# Programmable_AC_Series_Limiter.net
KiCad netlist of a schematic drawn in EAGLE
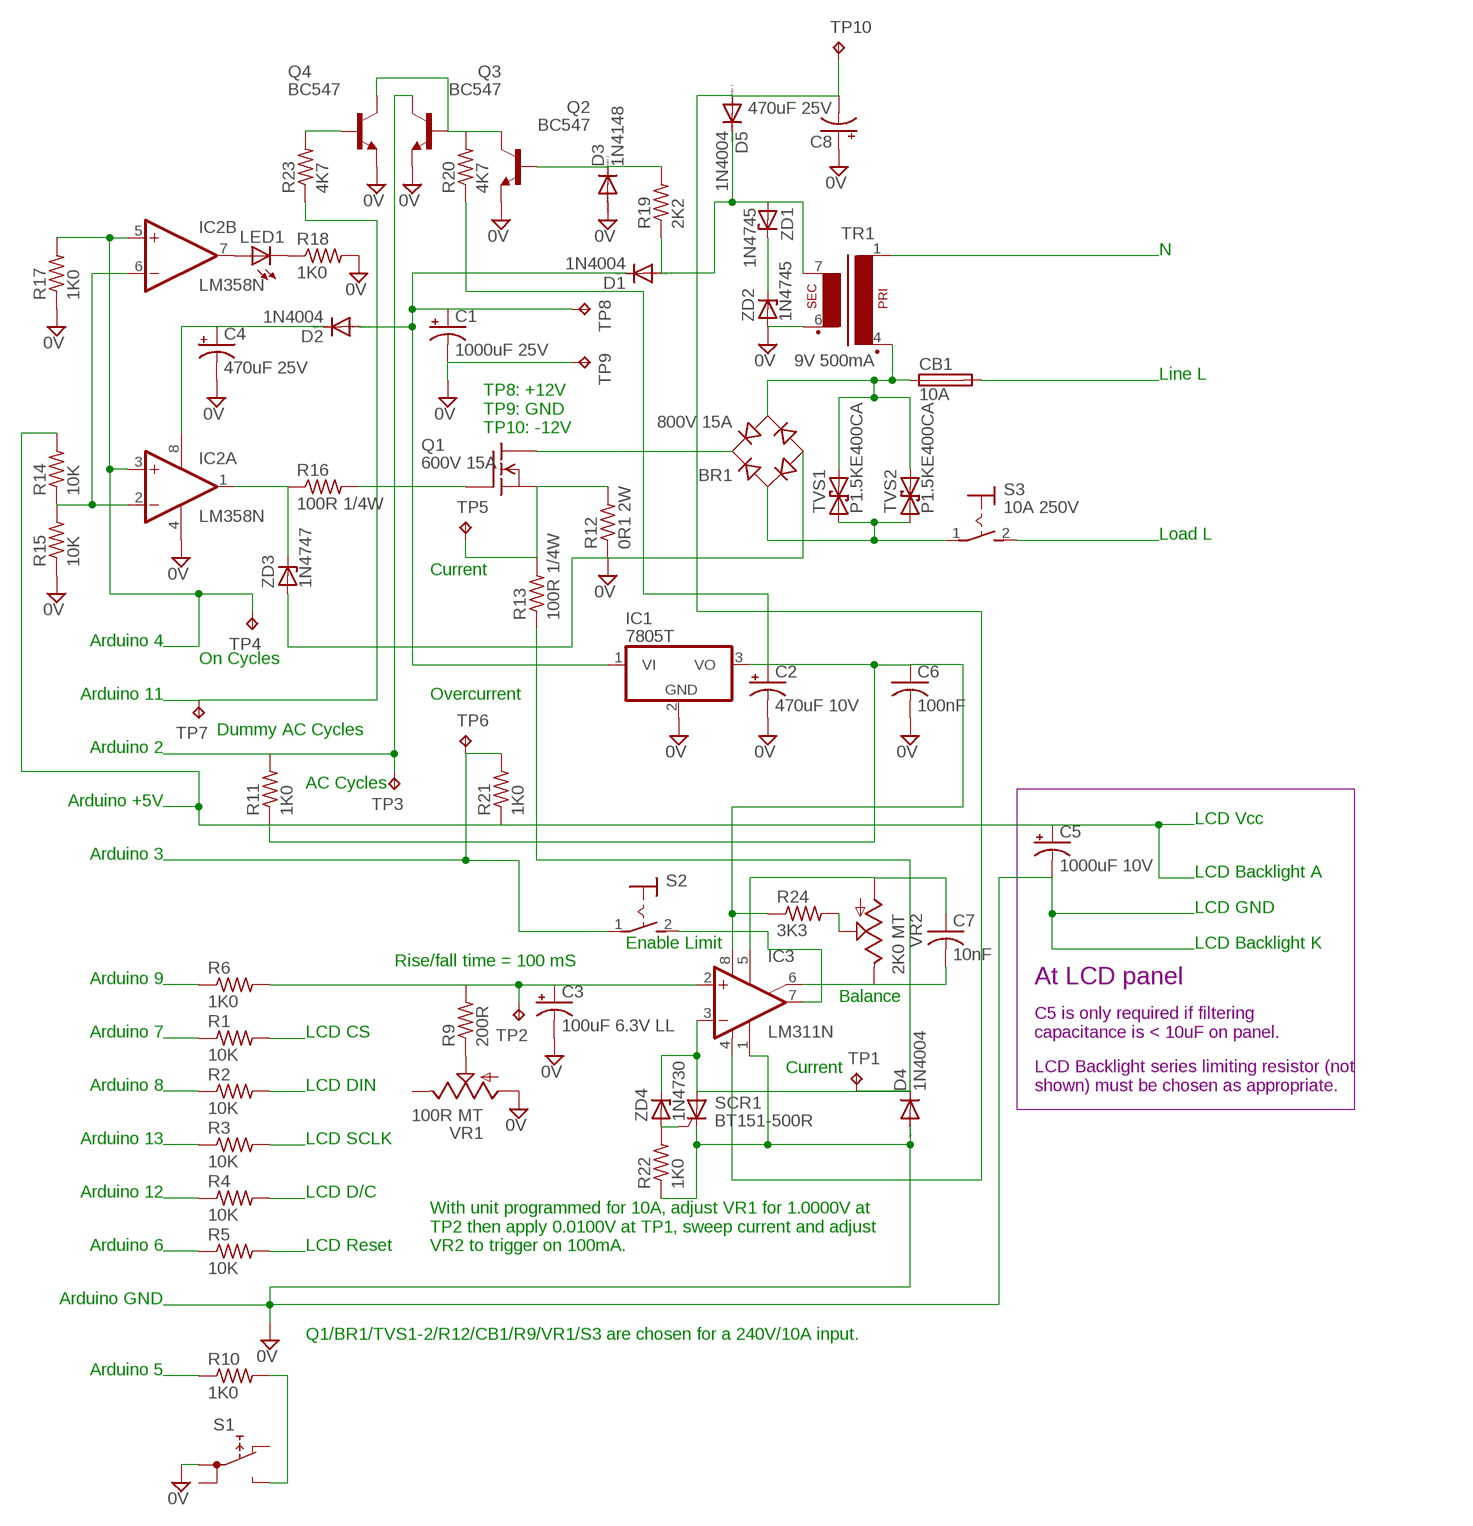
[diagram p0: schematic, sheet 1]

(export (version "E")
  (design (tool "Eeschema 10.0.6"))
  (components
    (comp (ref "BR1")
      (value "800V 15A")
      (footprint "eagle-import:DB")
      (libsource (lib "eagle-import") (part "DB?GDB101"))
    )
    (comp (ref "C1")
      (value "1000uF 25V")
      (footprint "eagle-import:B45181A")
      (libsource (lib "eagle-import") (part "CPOL-USB45181A"))
    )
    (comp (ref "C2")
      (value "470uF 10V")
      (footprint "eagle-import:B45181A")
      (libsource (lib "eagle-import") (part "CPOL-USB45181A"))
    )
    (comp (ref "C3")
      (value "100uF 6.3V LL")
      (footprint "eagle-import:B45181A")
      (libsource (lib "eagle-import") (part "CPOL-USB45181A"))
    )
    (comp (ref "C4")
      (value "470uF 25V")
      (footprint "eagle-import:B45181A")
      (libsource (lib "eagle-import") (part "CPOL-USB45181A"))
    )
    (comp (ref "C5")
      (value "1000uF 10V")
      (footprint "eagle-import:B45181A")
      (libsource (lib "eagle-import") (part "CPOL-USB45181A"))
    )
    (comp (ref "C6")
      (value "100nF")
      (footprint "eagle-import:C025-024X044")
      (libsource (lib "eagle-import") (part "C-US025-024X044"))
    )
    (comp (ref "C7")
      (value "10nF")
      (footprint "eagle-import:C025-024X044")
      (libsource (lib "eagle-import") (part "C-US025-024X044"))
    )
    (comp (ref "C8")
      (value "470uF 25V")
      (footprint "eagle-import:B45181A")
      (libsource (lib "eagle-import") (part "CPOL-USB45181A"))
    )
    (comp (ref "CB1")
      (value "10A")
      (footprint "eagle-import:FUSE_HOLDER_MENTOR-1821")
      (libsource (lib "eagle-import") (part "FUSE1821"))
    )
    (comp (ref "D1")
      (value "1N4004")
      (footprint "eagle-import:DO41-10")
      (libsource (lib "eagle-import") (part "1N4004"))
    )
    (comp (ref "D2")
      (value "1N4004")
      (footprint "eagle-import:DO41-10")
      (libsource (lib "eagle-import") (part "1N4004"))
    )
    (comp (ref "D3")
      (value "1N4148")
      (footprint "eagle-import:DO35-7")
      (libsource (lib "eagle-import") (part "1N4148DO35-7"))
    )
    (comp (ref "D4")
      (value "1N4004")
      (footprint "eagle-import:DO41-10")
      (libsource (lib "eagle-import") (part "1N4004"))
    )
    (comp (ref "D5")
      (value "1N4004")
      (footprint "eagle-import:DO41-10")
      (libsource (lib "eagle-import") (part "1N4004"))
    )
    (comp (ref "IC1")
      (value "7805T")
      (footprint "eagle-import:TO220H")
      (libsource (lib "eagle-import") (part "78T05"))
    )
    (comp (ref "IC2")
      (value "LM358N")
      (footprint "eagle-import:DIL08")
      (libsource (lib "eagle-import") (part "LM358N"))
    )
    (comp (ref "IC3")
      (value "LM311N")
      (footprint "eagle-import:DIL08")
      (libsource (lib "eagle-import") (part "LM311N"))
    )
    (comp (ref "LED1")
      (value "LED5MM")
      (footprint "eagle-import:LED5MM")
      (libsource (lib "eagle-import") (part "LED5MM"))
    )
    (comp (ref "Q1")
      (value "600V 15A")
      (footprint "eagle-import:TO220")
      (libsource (lib "eagle-import") (part "BUZ21"))
    )
    (comp (ref "Q2")
      (value "BC547")
      (footprint "eagle-import:TO92")
      (libsource (lib "eagle-import") (part "BC547"))
    )
    (comp (ref "Q3")
      (value "BC547")
      (footprint "eagle-import:TO92")
      (libsource (lib "eagle-import") (part "BC547"))
    )
    (comp (ref "Q4")
      (value "BC547")
      (footprint "eagle-import:TO92")
      (libsource (lib "eagle-import") (part "BC547"))
    )
    (comp (ref "R1")
      (value "10K")
      (footprint "eagle-import:0204V")
      (libsource (lib "eagle-import") (part "R-US_0204/2V"))
    )
    (comp (ref "R2")
      (value "10K")
      (footprint "eagle-import:0204V")
      (libsource (lib "eagle-import") (part "R-US_0204/2V"))
    )
    (comp (ref "R3")
      (value "10K")
      (footprint "eagle-import:0204V")
      (libsource (lib "eagle-import") (part "R-US_0204/2V"))
    )
    (comp (ref "R4")
      (value "10K")
      (footprint "eagle-import:0204V")
      (libsource (lib "eagle-import") (part "R-US_0204/2V"))
    )
    (comp (ref "R5")
      (value "10K")
      (footprint "eagle-import:0204V")
      (libsource (lib "eagle-import") (part "R-US_0204/2V"))
    )
    (comp (ref "R6")
      (value "1K0")
      (footprint "eagle-import:0204V")
      (libsource (lib "eagle-import") (part "R-US_0204/2V"))
    )
    (comp (ref "R9")
      (value "200R")
      (footprint "eagle-import:0204V")
      (libsource (lib "eagle-import") (part "R-US_0204/2V"))
    )
    (comp (ref "R10")
      (value "1K0")
      (footprint "eagle-import:0204V")
      (libsource (lib "eagle-import") (part "R-US_0204/2V"))
    )
    (comp (ref "R11")
      (value "1K0")
      (footprint "eagle-import:0204V")
      (libsource (lib "eagle-import") (part "R-US_0204/2V"))
    )
    (comp (ref "R12")
      (value "0R1 2W")
      (footprint "eagle-import:0204V")
      (libsource (lib "eagle-import") (part "R-US_0204/2V"))
    )
    (comp (ref "R13")
      (value "100R 1/4W")
      (footprint "eagle-import:0204V")
      (libsource (lib "eagle-import") (part "R-US_0204/2V"))
    )
    (comp (ref "R14")
      (value "10K")
      (footprint "eagle-import:0204V")
      (libsource (lib "eagle-import") (part "R-US_0204/2V"))
    )
    (comp (ref "R15")
      (value "10K")
      (footprint "eagle-import:0204V")
      (libsource (lib "eagle-import") (part "R-US_0204/2V"))
    )
    (comp (ref "R16")
      (value "100R 1/4W")
      (footprint "eagle-import:0204V")
      (libsource (lib "eagle-import") (part "R-US_0204/2V"))
    )
    (comp (ref "R17")
      (value "1K0")
      (footprint "eagle-import:0204V")
      (libsource (lib "eagle-import") (part "R-US_0204/2V"))
    )
    (comp (ref "R18")
      (value "1K0")
      (footprint "eagle-import:0204V")
      (libsource (lib "eagle-import") (part "R-US_0204/2V"))
    )
    (comp (ref "R19")
      (value "2K2")
      (footprint "eagle-import:0204V")
      (libsource (lib "eagle-import") (part "R-US_0204/2V"))
    )
    (comp (ref "R20")
      (value "4K7")
      (footprint "eagle-import:0204V")
      (libsource (lib "eagle-import") (part "R-US_0204/2V"))
    )
    (comp (ref "R21")
      (value "1K0")
      (footprint "eagle-import:0204V")
      (libsource (lib "eagle-import") (part "R-US_0204/2V"))
    )
    (comp (ref "R22")
      (value "1K0")
      (footprint "eagle-import:0204V")
      (libsource (lib "eagle-import") (part "R-US_0204/2V"))
    )
    (comp (ref "R23")
      (value "4K7")
      (footprint "eagle-import:0204V")
      (libsource (lib "eagle-import") (part "R-US_0204/2V"))
    )
    (comp (ref "R24")
      (value "3K3")
      (footprint "eagle-import:0204V")
      (libsource (lib "eagle-import") (part "R-US_0204/2V"))
    )
    (comp (ref "S1")
      (value "5501")
      (footprint "eagle-import:5501")
      (libsource (lib "eagle-import") (part "55?01"))
    )
    (comp (ref "S2")
      (value "MS243")
      (footprint "eagle-import:MS243")
      (libsource (lib "eagle-import") (part "MS243"))
    )
    (comp (ref "S3")
      (value "10A 250V")
      (footprint "eagle-import:MS243")
      (libsource (lib "eagle-import") (part "MS243"))
    )
    (comp (ref "SCR1")
      (value "BT151-500R")
      (footprint "eagle-import:TO220CL")
      (libsource (lib "eagle-import") (part "BT151"))
    )
    (comp (ref "TP1")
      (value "TPB1,27")
      (footprint "eagle-import:B1,27")
      (libsource (lib "eagle-import") (part "TPB1,27"))
    )
    (comp (ref "TP2")
      (value "TPB1,27")
      (footprint "eagle-import:B1,27")
      (libsource (lib "eagle-import") (part "TPB1,27"))
    )
    (comp (ref "TP3")
      (value "TPB1,27")
      (footprint "eagle-import:B1,27")
      (libsource (lib "eagle-import") (part "TPB1,27"))
    )
    (comp (ref "TP4")
      (value "TPB1,27")
      (footprint "eagle-import:B1,27")
      (libsource (lib "eagle-import") (part "TPB1,27"))
    )
    (comp (ref "TP5")
      (value "TPB1,27")
      (footprint "eagle-import:B1,27")
      (libsource (lib "eagle-import") (part "TPB1,27"))
    )
    (comp (ref "TP6")
      (value "TPB1,27")
      (footprint "eagle-import:B1,27")
      (libsource (lib "eagle-import") (part "TPB1,27"))
    )
    (comp (ref "TP7")
      (value "TPB1,27")
      (footprint "eagle-import:B1,27")
      (libsource (lib "eagle-import") (part "TPB1,27"))
    )
    (comp (ref "TP8")
      (value "TPB1,27")
      (footprint "eagle-import:B1,27")
      (libsource (lib "eagle-import") (part "TPB1,27"))
    )
    (comp (ref "TP9")
      (value "TPB1,27")
      (footprint "eagle-import:B1,27")
      (libsource (lib "eagle-import") (part "TPB1,27"))
    )
    (comp (ref "TP10")
      (value "TPB1,27")
      (footprint "eagle-import:B1,27")
      (libsource (lib "eagle-import") (part "TPB1,27"))
    )
    (comp (ref "TR1")
      (value "9V 500mA")
      (footprint "eagle-import:EE20-1")
      (libsource (lib "eagle-import") (part "EE20-1"))
    )
    (comp (ref "TVS1")
      (value "P1.5KE400CA")
      (footprint "eagle-import:CB417-15")
      (libsource (lib "eagle-import") (part "P6KEXXC"))
    )
    (comp (ref "TVS2")
      (value "P1.5KE400CA")
      (footprint "eagle-import:CB417-15")
      (libsource (lib "eagle-import") (part "P6KEXXC"))
    )
    (comp (ref "VR1")
      (value "100R MT")
      (footprint "eagle-import:EVUE")
      (libsource (lib "eagle-import") (part "US-EVUE2A"))
    )
    (comp (ref "VR2")
      (value "2K0 MT")
      (footprint "eagle-import:EVUE")
      (libsource (lib "eagle-import") (part "US-EVUE2A"))
    )
    (comp (ref "ZD1")
      (value "1N4745")
      (footprint "eagle-import:C1702-15")
      (libsource (lib "eagle-import") (part "ZENER-DIODEC1702-15"))
    )
    (comp (ref "ZD2")
      (value "1N4745")
      (footprint "eagle-import:C1702-15")
      (libsource (lib "eagle-import") (part "ZENER-DIODEC1702-15"))
    )
    (comp (ref "ZD3")
      (value "1N4747")
      (footprint "eagle-import:C1702-15")
      (libsource (lib "eagle-import") (part "ZENER-DIODEC1702-15"))
    )
    (comp (ref "ZD4")
      (value "1N4730")
      (footprint "eagle-import:C1702-15")
      (libsource (lib "eagle-import") (part "ZENER-DIODEC1702-15"))
    )
  )
  (nets
    (net (code "1") (name "0V") (class "Default")
      (node (ref "BR1") (pin "-") (pinfunction "-_-") (pintype "passive"))
      (node (ref "C1") (pin "-") (pinfunction "-_-") (pintype "passive"))
      (node (ref "C2") (pin "-") (pinfunction "-_-") (pintype "passive"))
      (node (ref "C3") (pin "-") (pinfunction "-_-") (pintype "passive"))
      (node (ref "C4") (pin "-") (pinfunction "-_-") (pintype "passive"))
      (node (ref "C5") (pin "-") (pinfunction "-_-") (pintype "passive"))
      (node (ref "C6") (pin "2") (pinfunction "2_2") (pintype "passive"))
      (node (ref "C8") (pin "+") (pinfunction "+_+") (pintype "passive"))
      (node (ref "D3") (pin "A") (pinfunction "A_A") (pintype "passive"))
      (node (ref "D4") (pin "A") (pinfunction "A_A") (pintype "passive"))
      (node (ref "IC1") (pin "2") (pinfunction "GND_2") (pintype "passive"))
      (node (ref "IC2") (pin "4") (pinfunction "V-_4") (pintype "power_in"))
      (node (ref "IC3") (pin "1") (pinfunction "GND_1") (pintype "passive"))
      (node (ref "Q2") (pin "1") (pinfunction "E_1") (pintype "passive"))
      (node (ref "Q3") (pin "1") (pinfunction "E_1") (pintype "passive"))
      (node (ref "Q4") (pin "1") (pinfunction "E_1") (pintype "passive"))
      (node (ref "R12") (pin "1") (pinfunction "1_1") (pintype "passive"))
      (node (ref "R15") (pin "1") (pinfunction "1_1") (pintype "passive"))
      (node (ref "R17") (pin "1") (pinfunction "1_1") (pintype "passive"))
      (node (ref "R18") (pin "2") (pinfunction "2_2") (pintype "passive"))
      (node (ref "R22") (pin "1") (pinfunction "1_1") (pintype "passive"))
      (node (ref "S1") (pin "1A") (pinfunction "1A_1A") (pintype "passive"))
      (node (ref "SCR1") (pin "C") (pinfunction "C_C") (pintype "passive"))
      (node (ref "TP9") (pin "TP") (pinfunction "TP_TP") (pintype "input"))
      (node (ref "TR1") (pin "6") (pinfunction "S3_6") (pintype "passive"))
      (node (ref "VR1") (pin "1") (pinfunction "A_1") (pintype "passive"))
      (node (ref "ZD2") (pin "A") (pinfunction "A_A") (pintype "passive"))
      (node (ref "ZD3") (pin "A") (pinfunction "A_A") (pintype "passive"))
    )
    (net (code "2") (name "Net-(CB1-1)") (class "Default")
      (node (ref "BR1") (pin "AC2") (pinfunction "AC2_AC2") (pintype "passive"))
      (node (ref "CB1") (pin "A") (pinfunction "1_A") (pintype "passive"))
      (node (ref "TR1") (pin "4") (pinfunction "P2_4") (pintype "passive"))
      (node (ref "TVS1") (pin "C") (pinfunction "2_C") (pintype "passive"))
      (node (ref "TVS2") (pin "C") (pinfunction "2_C") (pintype "passive"))
    )
    (net (code "3") (name "Net-(IC1-VI)") (class "Default")
      (node (ref "C1") (pin "+") (pinfunction "+_+") (pintype "passive"))
      (node (ref "D1") (pin "C") (pinfunction "C_C") (pintype "passive"))
      (node (ref "D2") (pin "A") (pinfunction "A_A") (pintype "passive"))
      (node (ref "IC1") (pin "1") (pinfunction "VI_1") (pintype "input"))
      (node (ref "TP8") (pin "TP") (pinfunction "TP_TP") (pintype "input"))
    )
    (net (code "4") (name "Net-(IC1-VO)") (class "Default")
      (node (ref "C2") (pin "+") (pinfunction "+_+") (pintype "passive"))
      (node (ref "C5") (pin "+") (pinfunction "+_+") (pintype "passive"))
      (node (ref "C6") (pin "1") (pinfunction "1_1") (pintype "passive"))
      (node (ref "IC1") (pin "3") (pinfunction "VO_3") (pintype "passive"))
      (node (ref "IC3") (pin "8") (pinfunction "V+_8") (pintype "power_in"))
      (node (ref "R11") (pin "1") (pinfunction "1_1") (pintype "passive"))
      (node (ref "R14") (pin "2") (pinfunction "2_2") (pintype "passive"))
      (node (ref "R20") (pin "1") (pinfunction "1_1") (pintype "passive"))
      (node (ref "R21") (pin "1") (pinfunction "1_1") (pintype "passive"))
      (node (ref "R24") (pin "1") (pinfunction "1_1") (pintype "passive"))
    )
    (net (code "5") (name "Net-(IC2A-+IN)") (class "Default")
      (node (ref "IC2") (pin "3") (pinfunction "+IN_3") (pintype "input"))
      (node (ref "IC2") (pin "5") (pinfunction "+IN_5") (pintype "input"))
      (node (ref "R17") (pin "2") (pinfunction "2_2") (pintype "passive"))
      (node (ref "TP4") (pin "TP") (pinfunction "TP_TP") (pintype "input"))
    )
    (net (code "6") (name "Net-(IC2A--IN)") (class "Default")
      (node (ref "IC2") (pin "2") (pinfunction "-IN_2") (pintype "input"))
      (node (ref "IC2") (pin "6") (pinfunction "-IN_6") (pintype "input"))
      (node (ref "R14") (pin "1") (pinfunction "1_1") (pintype "passive"))
      (node (ref "R15") (pin "2") (pinfunction "2_2") (pintype "passive"))
    )
    (net (code "7") (name "Net-(IC2A-OUT)") (class "Default")
      (node (ref "IC2") (pin "1") (pinfunction "OUT_1") (pintype "output"))
      (node (ref "R16") (pin "1") (pinfunction "1_1") (pintype "passive"))
      (node (ref "ZD3") (pin "C") (pinfunction "C_C") (pintype "passive"))
    )
    (net (code "8") (name "Net-(IC2B-OUT)") (class "Default")
      (node (ref "IC2") (pin "7") (pinfunction "OUT_7") (pintype "output"))
      (node (ref "LED1") (pin "A") (pinfunction "A_A") (pintype "passive"))
    )
    (net (code "9") (name "Net-(IC2C-V+)") (class "Default")
      (node (ref "C4") (pin "+") (pinfunction "+_+") (pintype "passive"))
      (node (ref "D2") (pin "C") (pinfunction "C_C") (pintype "passive"))
      (node (ref "IC2") (pin "8") (pinfunction "V+_8") (pintype "power_in"))
    )
    (net (code "10") (name "Net-(IC3-+IN)") (class "Default")
      (node (ref "C3") (pin "+") (pinfunction "+_+") (pintype "passive"))
      (node (ref "IC3") (pin "2") (pinfunction "+IN_2") (pintype "input"))
      (node (ref "R6") (pin "2") (pinfunction "2_2") (pintype "passive"))
      (node (ref "R9") (pin "2") (pinfunction "2_2") (pintype "passive"))
      (node (ref "TP2") (pin "TP") (pinfunction "TP_TP") (pintype "input"))
    )
    (net (code "11") (name "Net-(IC3--IN)") (class "Default")
      (node (ref "D4") (pin "C") (pinfunction "C_C") (pintype "passive"))
      (node (ref "IC3") (pin "3") (pinfunction "-IN_3") (pintype "input"))
      (node (ref "R13") (pin "1") (pinfunction "1_1") (pintype "passive"))
      (node (ref "SCR1") (pin "A") (pinfunction "A_A") (pintype "passive"))
      (node (ref "TP1") (pin "TP") (pinfunction "TP_TP") (pintype "input"))
      (node (ref "ZD4") (pin "C") (pinfunction "C_C") (pintype "passive"))
    )
    (net (code "12") (name "Net-(IC3-ON)") (class "Default")
      (node (ref "C7") (pin "1") (pinfunction "1_1") (pintype "passive"))
      (node (ref "IC3") (pin "5") (pinfunction "ON_5") (pintype "passive"))
      (node (ref "VR2") (pin "1") (pinfunction "A_1") (pintype "passive"))
    )
    (net (code "13") (name "Net-(IC3-ON{slash}STR)") (class "Default")
      (node (ref "C7") (pin "2") (pinfunction "2_2") (pintype "passive"))
      (node (ref "IC3") (pin "6") (pinfunction "ON/STR_6") (pintype "passive"))
      (node (ref "VR2") (pin "3") (pinfunction "E_3") (pintype "passive"))
    )
    (net (code "14") (name "Net-(IC3-OUT)") (class "Default")
      (node (ref "IC3") (pin "7") (pinfunction "OUT_7") (pintype "output"))
      (node (ref "S2") (pin "2") (pinfunction "S_2") (pintype "passive"))
    )
    (net (code "15") (name "Net-(IC3-V-)") (class "Default")
      (node (ref "C8") (pin "-") (pinfunction "-_-") (pintype "passive"))
      (node (ref "D5") (pin "A") (pinfunction "A_A") (pintype "passive"))
      (node (ref "IC3") (pin "4") (pinfunction "V-_4") (pintype "power_in"))
      (node (ref "TP10") (pin "TP") (pinfunction "TP_TP") (pintype "input"))
    )
    (net (code "16") (name "Net-(LED1-C)") (class "Default")
      (node (ref "LED1") (pin "K") (pinfunction "C_K") (pintype "passive"))
      (node (ref "R18") (pin "1") (pinfunction "1_1") (pintype "passive"))
    )
    (net (code "17") (name "Net-(Q1-D)") (class "Default")
      (node (ref "BR1") (pin "+") (pinfunction "+_+") (pintype "passive"))
      (node (ref "Q1") (pin "2") (pinfunction "D_2") (pintype "passive"))
    )
    (net (code "18") (name "Net-(Q1-G)") (class "Default")
      (node (ref "Q1") (pin "1") (pinfunction "G_1") (pintype "passive"))
      (node (ref "R16") (pin "2") (pinfunction "2_2") (pintype "passive"))
    )
    (net (code "19") (name "Net-(Q1-S)") (class "Default")
      (node (ref "Q1") (pin "3") (pinfunction "S_3") (pintype "passive"))
      (node (ref "R12") (pin "2") (pinfunction "2_2") (pintype "passive"))
      (node (ref "R13") (pin "2") (pinfunction "2_2") (pintype "passive"))
      (node (ref "TP5") (pin "TP") (pinfunction "TP_TP") (pintype "input"))
    )
    (net (code "20") (name "Net-(Q2-B)") (class "Default")
      (node (ref "D3") (pin "C") (pinfunction "C_C") (pintype "passive"))
      (node (ref "Q2") (pin "2") (pinfunction "B_2") (pintype "passive"))
      (node (ref "R19") (pin "2") (pinfunction "2_2") (pintype "passive"))
    )
    (net (code "21") (name "Net-(Q2-C)") (class "Default")
      (node (ref "Q2") (pin "3") (pinfunction "C_3") (pintype "passive"))
      (node (ref "Q3") (pin "2") (pinfunction "B_2") (pintype "passive"))
      (node (ref "Q4") (pin "3") (pinfunction "C_3") (pintype "passive"))
      (node (ref "R20") (pin "2") (pinfunction "2_2") (pintype "passive"))
    )
    (net (code "22") (name "Net-(Q3-C)") (class "Default")
      (node (ref "Q3") (pin "3") (pinfunction "C_3") (pintype "passive"))
      (node (ref "R11") (pin "2") (pinfunction "2_2") (pintype "passive"))
      (node (ref "TP3") (pin "TP") (pinfunction "TP_TP") (pintype "input"))
    )
    (net (code "23") (name "Net-(Q4-B)") (class "Default")
      (node (ref "Q4") (pin "2") (pinfunction "B_2") (pintype "passive"))
      (node (ref "R23") (pin "2") (pinfunction "2_2") (pintype "passive"))
    )
    (net (code "24") (name "Net-(R10-Pad2)") (class "Default")
      (node (ref "R10") (pin "2") (pinfunction "2_2") (pintype "passive"))
      (node (ref "S1") (pin "NO") (pinfunction "NO_NO") (pintype "passive"))
    )
    (net (code "25") (name "Net-(R22-Pad2)") (class "Default")
      (node (ref "R22") (pin "2") (pinfunction "2_2") (pintype "passive"))
      (node (ref "SCR1") (pin "G") (pinfunction "G_G") (pintype "passive"))
      (node (ref "ZD4") (pin "A") (pinfunction "A_A") (pintype "passive"))
    )
    (net (code "26") (name "Net-(R23-Pad1)") (class "Default")
      (node (ref "R23") (pin "1") (pinfunction "1_1") (pintype "passive"))
      (node (ref "TP7") (pin "TP") (pinfunction "TP_TP") (pintype "input"))
    )
    (net (code "27") (name "Net-(S2-P)") (class "Default")
      (node (ref "R21") (pin "2") (pinfunction "2_2") (pintype "passive"))
      (node (ref "S2") (pin "1") (pinfunction "P_1") (pintype "passive"))
      (node (ref "TP6") (pin "TP") (pinfunction "TP_TP") (pintype "input"))
    )
    (net (code "28") (name "Net-(S3-P)") (class "Default")
      (node (ref "BR1") (pin "AC1") (pinfunction "AC1_AC1") (pintype "passive"))
      (node (ref "S3") (pin "1") (pinfunction "P_1") (pintype "passive"))
      (node (ref "TVS1") (pin "A") (pinfunction "1_A") (pintype "passive"))
      (node (ref "TVS2") (pin "A") (pinfunction "1_A") (pintype "passive"))
    )
    (net (code "29") (name "Net-(TR1-S4)") (class "Default")
      (node (ref "D1") (pin "A") (pinfunction "A_A") (pintype "passive"))
      (node (ref "D5") (pin "C") (pinfunction "C_C") (pintype "passive"))
      (node (ref "R19") (pin "1") (pinfunction "1_1") (pintype "passive"))
      (node (ref "TR1") (pin "7") (pinfunction "S4_7") (pintype "passive"))
      (node (ref "ZD1") (pin "A") (pinfunction "A_A") (pintype "passive"))
    )
    (net (code "30") (name "Net-(VR1-S)") (class "Default")
      (node (ref "R9") (pin "1") (pinfunction "1_1") (pintype "passive"))
      (node (ref "VR1") (pin "2") (pinfunction "S_2") (pintype "passive"))
    )
    (net (code "31") (name "Net-(VR2-S)") (class "Default")
      (node (ref "R24") (pin "2") (pinfunction "2_2") (pintype "passive"))
      (node (ref "VR2") (pin "2") (pinfunction "S_2") (pintype "passive"))
    )
    (net (code "32") (name "Net-(ZD1-PadC)") (class "Default")
      (node (ref "ZD1") (pin "C") (pinfunction "C_C") (pintype "passive"))
      (node (ref "ZD2") (pin "C") (pinfunction "C_C") (pintype "passive"))
    )
    (net (code "33") (name "unconnected-(CB1-2-PadB)") (class "Default")
      (node (ref "CB1") (pin "B") (pinfunction "2_B") (pintype "passive"))
    )
    (net (code "34") (name "unconnected-(R1-Pad1)") (class "Default")
      (node (ref "R1") (pin "1") (pinfunction "1_1") (pintype "passive"))
    )
    (net (code "35") (name "unconnected-(R1-Pad2)") (class "Default")
      (node (ref "R1") (pin "2") (pinfunction "2_2") (pintype "passive"))
    )
    (net (code "36") (name "unconnected-(R2-Pad1)") (class "Default")
      (node (ref "R2") (pin "1") (pinfunction "1_1") (pintype "passive"))
    )
    (net (code "37") (name "unconnected-(R2-Pad2)") (class "Default")
      (node (ref "R2") (pin "2") (pinfunction "2_2") (pintype "passive"))
    )
    (net (code "38") (name "unconnected-(R3-Pad1)") (class "Default")
      (node (ref "R3") (pin "1") (pinfunction "1_1") (pintype "passive"))
    )
    (net (code "39") (name "unconnected-(R3-Pad2)") (class "Default")
      (node (ref "R3") (pin "2") (pinfunction "2_2") (pintype "passive"))
    )
    (net (code "40") (name "unconnected-(R4-Pad1)") (class "Default")
      (node (ref "R4") (pin "1") (pinfunction "1_1") (pintype "passive"))
    )
    (net (code "41") (name "unconnected-(R4-Pad2)") (class "Default")
      (node (ref "R4") (pin "2") (pinfunction "2_2") (pintype "passive"))
    )
    (net (code "42") (name "unconnected-(R5-Pad1)") (class "Default")
      (node (ref "R5") (pin "1") (pinfunction "1_1") (pintype "passive"))
    )
    (net (code "43") (name "unconnected-(R5-Pad2)") (class "Default")
      (node (ref "R5") (pin "2") (pinfunction "2_2") (pintype "passive"))
    )
    (net (code "44") (name "unconnected-(R6-Pad1)") (class "Default")
      (node (ref "R6") (pin "1") (pinfunction "1_1") (pintype "passive"))
    )
    (net (code "45") (name "unconnected-(R10-Pad1)") (class "Default")
      (node (ref "R10") (pin "1") (pinfunction "1_1") (pintype "passive"))
    )
    (net (code "46") (name "unconnected-(S1-Pad1B)") (class "Default")
      (node (ref "S1") (pin "1B") (pinfunction "1B_1B") (pintype "passive"))
    )
    (net (code "47") (name "unconnected-(S1-PadNC)") (class "Default")
      (node (ref "S1") (pin "NC") (pinfunction "NC_NC") (pintype "passive"))
    )
    (net (code "48") (name "unconnected-(S3-S-Pad2)") (class "Default")
      (node (ref "S3") (pin "2") (pinfunction "S_2") (pintype "passive"))
    )
    (net (code "49") (name "unconnected-(TR1-P1-Pad1)") (class "Default")
      (node (ref "TR1") (pin "1") (pinfunction "P1_1") (pintype "passive"))
    )
    (net (code "50") (name "unconnected-(VR1-E-Pad3)") (class "Default")
      (node (ref "VR1") (pin "3") (pinfunction "E_3") (pintype "passive"))
    )
  )
)
